# Sensors.net
KiCad netlist of a schematic drawn in Altium Designer
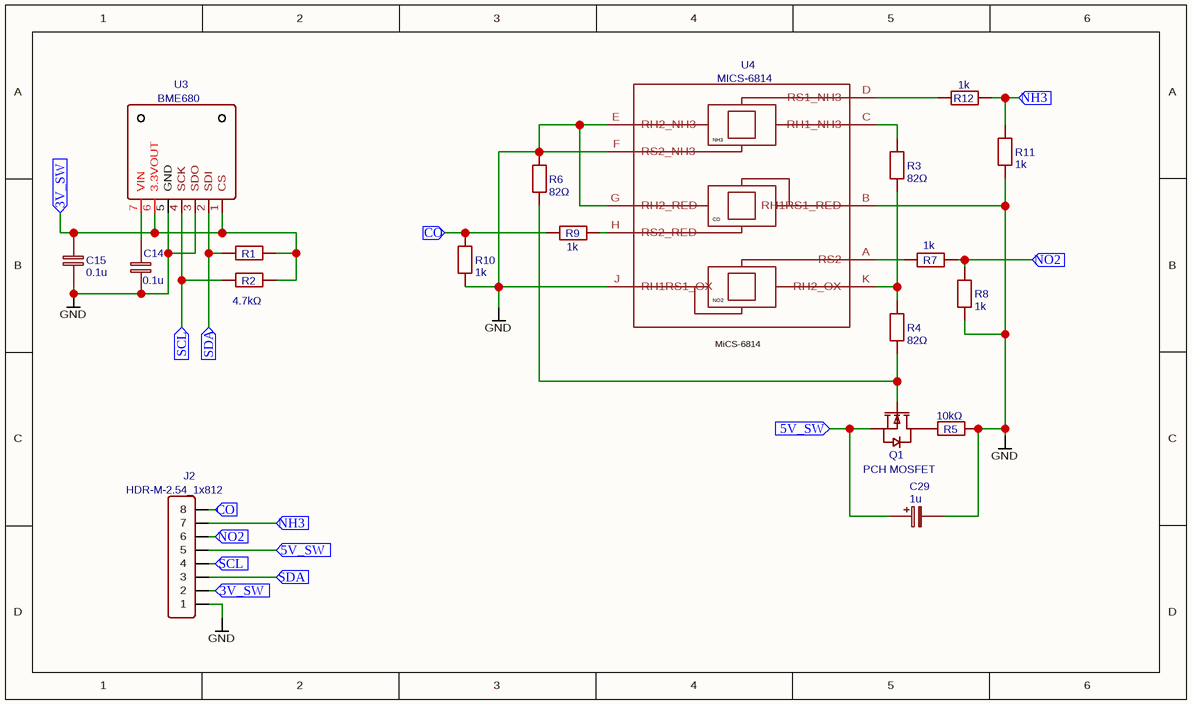
[diagram p0: Sensors.schdoc]

(export (version "E")
  (design (tool "Eeschema 10.0.6"))
  (components
    (comp (ref "C14")
      (value "0.1u")
      (fields (field (name "CONTRIBUTOR") "LCEDA_Lib"))
      (libsource (lib "altium-import") (part "root_1_0.1u_"))
    )
    (comp (ref "C15")
      (value "0.1u")
      (fields (field (name "CONTRIBUTOR") "LCEDA_Lib"))
      (libsource (lib "altium-import") (part "root_1_0.1u_"))
    )
    (comp (ref "C29")
      (value "1u")
      (fields (field (name "CONTRIBUTOR") "LCEDA_Lib"))
      (libsource (lib "altium-import") (part "root_0_1u_"))
    )
    (comp (ref "J2")
      (value "HDR-M-2.54_1x812")
      (fields (field (name "BOM_SUPPLIER PART") "C190820") (field (name "CONTRIBUTOR") "Hane_Jared"))
      (libsource (lib "altium-import") (part "root_2_HDR-M-2.54_1x812_"))
    )
    (comp (ref "Q1")
      (value "PCH MOSFET")
      (fields
        (field (name "BOM_SUPPLIER PART") "C516873")
        (field (name "BOM_MANUFACTURER PART") "VB1240B")
        (field (name "CONTRIBUTOR") "LCSC")
      )
      (libsource (lib "altium-import") (part "root_3_PCH MOSFET_"))
    )
    (comp (ref "R1")
      (value "4.7kΩ")
      (fields
        (field (name "BOM_SUPPLIER PART") "C517493")
        (field (name "BOM_MANUFACTURER PART") "TC0350D4701T5H")
        (field (name "CONTRIBUTOR") "LCSC")
      )
      (libsource (lib "altium-import") (part "root_2_4.7kΩ_"))
    )
    (comp (ref "R2")
      (value "4.7kΩ")
      (fields
        (field (name "BOM_SUPPLIER PART") "C517493")
        (field (name "BOM_MANUFACTURER PART") "TC0350D4701T5H")
        (field (name "CONTRIBUTOR") "LCSC")
      )
      (libsource (lib "altium-import") (part "root_2_4.7kΩ_"))
    )
    (comp (ref "R3")
      (value "82Ω")
      (fields
        (field (name "BOM_SUPPLIER PART") "C525388")
        (field (name "BOM_MANUFACTURER PART") "TCTR0603F47K0F3960T")
        (field (name "CONTRIBUTOR") "LCSC")
      )
      (libsource (lib "altium-import") (part "root_1_82Ω_"))
    )
    (comp (ref "R4")
      (value "82Ω")
      (fields
        (field (name "BOM_SUPPLIER PART") "C525388")
        (field (name "BOM_MANUFACTURER PART") "TCTR0603F47K0F3960T")
        (field (name "CONTRIBUTOR") "LCSC")
      )
      (libsource (lib "altium-import") (part "root_1_82Ω_"))
    )
    (comp (ref "R5")
      (value "10kΩ")
      (fields
        (field (name "BOM_SUPPLIER PART") "C525388")
        (field (name "BOM_MANUFACTURER PART") "TCTR0603F47K0F3960T")
        (field (name "CONTRIBUTOR") "LCSC")
      )
      (libsource (lib "altium-import") (part "root_2_10kΩ_"))
    )
    (comp (ref "R6")
      (value "82Ω")
      (fields
        (field (name "BOM_SUPPLIER PART") "C525388")
        (field (name "BOM_MANUFACTURER PART") "TCTR0603F47K0F3960T")
        (field (name "CONTRIBUTOR") "LCSC")
      )
      (libsource (lib "altium-import") (part "root_3_82Ω_"))
    )
    (comp (ref "R7")
      (value "1k")
      (fields (field (name "CONTRIBUTOR") "LCEDA_Lib"))
      (libsource (lib "altium-import") (part "root_0_1k_"))
    )
    (comp (ref "R8")
      (value "1k")
      (fields (field (name "CONTRIBUTOR") "LCEDA_Lib"))
      (libsource (lib "altium-import") (part "root_1_1k_"))
    )
    (comp (ref "R9")
      (value "1k")
      (fields (field (name "CONTRIBUTOR") "LCEDA_Lib"))
      (libsource (lib "altium-import") (part "root_0_1k_"))
    )
    (comp (ref "R10")
      (value "1k")
      (fields (field (name "CONTRIBUTOR") "LCEDA_Lib"))
      (libsource (lib "altium-import") (part "root_3_1k_"))
    )
    (comp (ref "R11")
      (value "1k")
      (fields (field (name "CONTRIBUTOR") "LCEDA_Lib"))
      (libsource (lib "altium-import") (part "root_3_1k_"))
    )
    (comp (ref "R12")
      (value "1k")
      (fields (field (name "CONTRIBUTOR") "LCEDA_Lib"))
      (libsource (lib "altium-import") (part "root_0_1k_"))
    )
    (comp (ref "U3")
      (value "BME680")
      (fields (field (name "BOM_SUPPLIER PART") "C125972") (field (name "CONTRIBUTOR") "mecopela"))
      (libsource (lib "altium-import") (part "root_1_BME680_"))
    )
    (comp (ref "U4")
      (value "MICS-6814")
      (description "314100015")
      (fields (field (name "CONTRIBUTOR") "sozturk"))
      (libsource (lib "altium-import") (part "root_0_MICS-6814_"))
    )
  )
  (nets
    (net (code "1") (name "/3V_SW") (class "Default")
      (node (ref "C15") (pin "2") (pinfunction "2_2") (pintype "passive"))
      (node (ref "J2") (pin "2") (pinfunction "2_2") (pintype "passive"))
      (node (ref "R1") (pin "1") (pinfunction "1_1") (pintype "passive"))
      (node (ref "R2") (pin "1") (pinfunction "1_1") (pintype "passive"))
      (node (ref "U3") (pin "1") (pinfunction "CS_1") (pintype "passive"))
      (node (ref "U3") (pin "6") (pinfunction "3.3VOUT_6") (pintype "passive"))
    )
    (net (code "2") (name "/5V_SW") (class "Default")
      (node (ref "C29") (pin "1") (pinfunction "1_1") (pintype "passive"))
      (node (ref "J2") (pin "5") (pinfunction "5_5") (pintype "passive"))
      (node (ref "Q1") (pin "2") (pinfunction "S_2") (pintype "passive"))
    )
    (net (code "3") (name "/CO") (class "Default")
      (node (ref "J2") (pin "8") (pinfunction "8_8") (pintype "passive"))
      (node (ref "R10") (pin "1") (pinfunction "1_1") (pintype "passive"))
      (node (ref "R9") (pin "1") (pinfunction "1_1") (pintype "passive"))
    )
    (net (code "4") (name "/NH3") (class "Default")
      (node (ref "J2") (pin "7") (pinfunction "7_7") (pintype "passive"))
      (node (ref "R11") (pin "1") (pinfunction "1_1") (pintype "passive"))
      (node (ref "R12") (pin "2") (pinfunction "2_2") (pintype "passive"))
    )
    (net (code "5") (name "/NO2") (class "Default")
      (node (ref "J2") (pin "6") (pinfunction "6_6") (pintype "passive"))
      (node (ref "R7") (pin "2") (pinfunction "2_2") (pintype "passive"))
      (node (ref "R8") (pin "2") (pinfunction "2_2") (pintype "passive"))
    )
    (net (code "6") (name "/SCL") (class "Default")
      (node (ref "J2") (pin "4") (pinfunction "4_4") (pintype "passive"))
      (node (ref "R2") (pin "2") (pinfunction "2_2") (pintype "passive"))
      (node (ref "U3") (pin "4") (pinfunction "SCK_4") (pintype "passive"))
    )
    (net (code "7") (name "/SDA") (class "Default")
      (node (ref "J2") (pin "3") (pinfunction "3_3") (pintype "passive"))
      (node (ref "R1") (pin "2") (pinfunction "2_2") (pintype "passive"))
      (node (ref "U3") (pin "2") (pinfunction "SDI_2") (pintype "passive"))
    )
    (net (code "8") (name "GND") (class "Default")
      (node (ref "C14") (pin "1") (pinfunction "1_1") (pintype "passive"))
      (node (ref "C15") (pin "1") (pinfunction "1_1") (pintype "passive"))
      (node (ref "C29") (pin "2") (pinfunction "2_2") (pintype "passive"))
      (node (ref "J2") (pin "1") (pinfunction "1_1") (pintype "passive"))
      (node (ref "R10") (pin "2") (pinfunction "2_2") (pintype "passive"))
      (node (ref "R11") (pin "2") (pinfunction "2_2") (pintype "passive"))
      (node (ref "R5") (pin "1") (pinfunction "1_1") (pintype "passive"))
      (node (ref "R6") (pin "1") (pinfunction "1_1") (pintype "passive"))
      (node (ref "R8") (pin "1") (pinfunction "1_1") (pintype "passive"))
      (node (ref "U3") (pin "3") (pinfunction "SDO_3") (pintype "passive"))
      (node (ref "U3") (pin "5") (pinfunction "GND_5") (pintype "passive"))
      (node (ref "U4") (pin "B") (pinfunction "RH1RS1_RED_B") (pintype "passive"))
      (node (ref "U4") (pin "E") (pinfunction "RH2_NH3_E") (pintype "passive"))
      (node (ref "U4") (pin "F") (pinfunction "RS2_NH3_F") (pintype "passive"))
      (node (ref "U4") (pin "G") (pinfunction "RH2_RED_G") (pintype "passive"))
      (node (ref "U4") (pin "J") (pinfunction "RH1RS1_OX_J") (pintype "passive"))
    )
    (net (code "9") (name "Net-(Q1-D)") (class "Default")
      (node (ref "Q1") (pin "3") (pinfunction "D_3") (pintype "passive"))
      (node (ref "R5") (pin "2") (pinfunction "2_2") (pintype "passive"))
    )
    (net (code "10") (name "Net-(Q1-G)") (class "Default")
      (node (ref "Q1") (pin "1") (pinfunction "G_1") (pintype "passive"))
      (node (ref "R4") (pin "1") (pinfunction "1_1") (pintype "passive"))
      (node (ref "R6") (pin "2") (pinfunction "2_2") (pintype "passive"))
    )
    (net (code "11") (name "Net-(U3-VIN)") (class "Default")
      (node (ref "C14") (pin "2") (pinfunction "2_2") (pintype "passive"))
      (node (ref "U3") (pin "7") (pinfunction "VIN_7") (pintype "passive"))
    )
    (net (code "12") (name "Net-(U4-RH1_NH3)") (class "Default")
      (node (ref "R3") (pin "2") (pinfunction "2_2") (pintype "passive"))
      (node (ref "U4") (pin "C") (pinfunction "RH1_NH3_C") (pintype "passive"))
    )
    (net (code "13") (name "Net-(U4-RH2_OX)") (class "Default")
      (node (ref "R3") (pin "1") (pinfunction "1_1") (pintype "passive"))
      (node (ref "R4") (pin "2") (pinfunction "2_2") (pintype "passive"))
      (node (ref "U4") (pin "K") (pinfunction "RH2_OX_K") (pintype "passive"))
    )
    (net (code "14") (name "Net-(U4-RS1_NH3)") (class "Default")
      (node (ref "R12") (pin "1") (pinfunction "1_1") (pintype "passive"))
      (node (ref "U4") (pin "D") (pinfunction "RS1_NH3_D") (pintype "passive"))
    )
    (net (code "15") (name "Net-(U4-RS2)") (class "Default")
      (node (ref "R7") (pin "1") (pinfunction "1_1") (pintype "passive"))
      (node (ref "U4") (pin "A") (pinfunction "RS2_A") (pintype "passive"))
    )
    (net (code "16") (name "Net-(U4-RS2_RED)") (class "Default")
      (node (ref "R9") (pin "2") (pinfunction "2_2") (pintype "passive"))
      (node (ref "U4") (pin "H") (pinfunction "RS2_RED_H") (pintype "passive"))
    )
  )
)
